# Experiment3.net
KiCad netlist of a schematic drawn in EAGLE
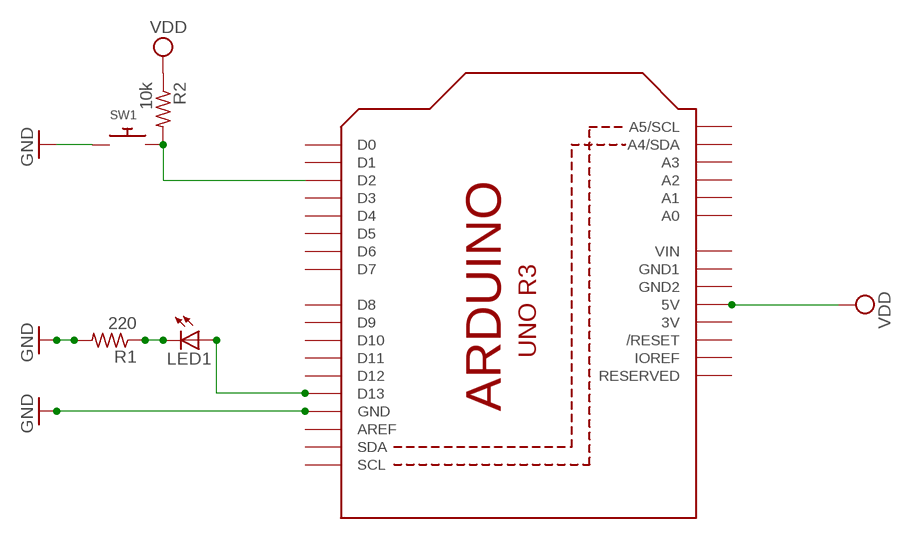
[diagram p0: schematic, sheet 1]

(export (version "E")
  (design (tool "Eeschema 10.0.6"))
  (components
    (comp (ref "LED1")
      (value "LED5MM")
      (footprint "eagle-import:LED5MM")
      (libsource (lib "eagle-import") (part "LED5MM"))
    )
    (comp (ref "R1")
      (value "220")
      (footprint "eagle-import:0204_5")
      (libsource (lib "eagle-import") (part "R-US_0204/5"))
    )
    (comp (ref "R2")
      (value "10k")
      (footprint "eagle-import:0204_5")
      (libsource (lib "eagle-import") (part "R-US_0204/5"))
    )
    (comp (ref "SW1")
      (value "SWITCH_PUSHBUTTONEVQ-PE")
      (footprint "eagle-import:TACT_PANA-EVQ")
      (libsource (lib "eagle-import") (part "SWITCH_PUSHBUTTONEVQ-PE"))
    )
    (comp (ref "U1")
      (value "ARDUINOR3-DIMENSION")
      (footprint "eagle-import:ARDUINOR3")
      (libsource (lib "eagle-import") (part "ARDUINOR3-DIMENSION"))
    )
  )
  (nets
    (net (code "1") (name "/3V") (class "Default")
      (node (ref "U1") (pin "3V") (pinfunction "3V_3V") (pintype "power_in"))
    )
    (net (code "2") (name "/GND1") (class "Default")
      (node (ref "U1") (pin "GND1") (pinfunction "GND1_GND1") (pintype "power_in"))
    )
    (net (code "3") (name "/GND2") (class "Default")
      (node (ref "U1") (pin "GND2") (pinfunction "GND2_GND2") (pintype "power_in"))
    )
    (net (code "4") (name "/VIN") (class "Default")
      (node (ref "U1") (pin "VIN") (pinfunction "VIN_VIN") (pintype "power_in"))
    )
    (net (code "5") (name "GND") (class "Default")
      (node (ref "R1") (pin "2") (pinfunction "2_2") (pintype "passive"))
      (node (ref "SW1") (pin "P$1") (pinfunction "P$1_P$1") (pintype "passive"))
      (node (ref "U1") (pin "GND") (pinfunction "GND_GND") (pintype "power_in"))
    )
    (net (code "6") (name "Net-(LED1-C)") (class "Default")
      (node (ref "LED1") (pin "K") (pinfunction "C_K") (pintype "passive"))
      (node (ref "R1") (pin "1") (pinfunction "1_1") (pintype "passive"))
    )
    (net (code "7") (name "Net-(LED1-PadA)") (class "Default")
      (node (ref "LED1") (pin "A") (pinfunction "A_A") (pintype "passive"))
      (node (ref "U1") (pin "D13") (pinfunction "D13_D13") (pintype "bidirectional"))
    )
    (net (code "8") (name "Net-(R2-Pad2)") (class "Default")
      (node (ref "R2") (pin "2") (pinfunction "2_2") (pintype "passive"))
      (node (ref "SW1") (pin "P$2") (pinfunction "P$2_P$2") (pintype "passive"))
      (node (ref "U1") (pin "D2") (pinfunction "D2_D2") (pintype "bidirectional"))
    )
    (net (code "9") (name "VDD") (class "Default")
      (node (ref "R2") (pin "1") (pinfunction "1_1") (pintype "passive"))
      (node (ref "U1") (pin "5V") (pinfunction "5V_5V") (pintype "power_in"))
    )
    (net (code "10") (name "unconnected-(U1-A4{slash}SDA-PadA4)") (class "Default")
      (node (ref "U1") (pin "A4") (pinfunction "A4/SDA_A4") (pintype "bidirectional"))
    )
    (net (code "11") (name "unconnected-(U1-A5{slash}SCL-PadA5)") (class "Default")
      (node (ref "U1") (pin "A5") (pinfunction "A5/SCL_A5") (pintype "bidirectional"))
    )
    (net (code "12") (name "unconnected-(U1-PadA0)") (class "Default")
      (node (ref "U1") (pin "A0") (pinfunction "A0_A0") (pintype "bidirectional"))
    )
    (net (code "13") (name "unconnected-(U1-PadA1)") (class "Default")
      (node (ref "U1") (pin "A1") (pinfunction "A1_A1") (pintype "bidirectional"))
    )
    (net (code "14") (name "unconnected-(U1-PadA2)") (class "Default")
      (node (ref "U1") (pin "A2") (pinfunction "A2_A2") (pintype "bidirectional"))
    )
    (net (code "15") (name "unconnected-(U1-PadA3)") (class "Default")
      (node (ref "U1") (pin "A3") (pinfunction "A3_A3") (pintype "bidirectional"))
    )
    (net (code "16") (name "unconnected-(U1-PadAREF)") (class "Default")
      (node (ref "U1") (pin "AREF") (pinfunction "AREF_AREF") (pintype "bidirectional"))
    )
    (net (code "17") (name "unconnected-(U1-PadD0)") (class "Default")
      (node (ref "U1") (pin "D0") (pinfunction "D0_D0") (pintype "bidirectional"))
    )
    (net (code "18") (name "unconnected-(U1-PadD1)") (class "Default")
      (node (ref "U1") (pin "D1") (pinfunction "D1_D1") (pintype "bidirectional"))
    )
    (net (code "19") (name "unconnected-(U1-PadD3)") (class "Default")
      (node (ref "U1") (pin "D3") (pinfunction "D3_D3") (pintype "bidirectional"))
    )
    (net (code "20") (name "unconnected-(U1-PadD4)") (class "Default")
      (node (ref "U1") (pin "D4") (pinfunction "D4_D4") (pintype "bidirectional"))
    )
    (net (code "21") (name "unconnected-(U1-PadD5)") (class "Default")
      (node (ref "U1") (pin "D5") (pinfunction "D5_D5") (pintype "bidirectional"))
    )
    (net (code "22") (name "unconnected-(U1-PadD6)") (class "Default")
      (node (ref "U1") (pin "D6") (pinfunction "D6_D6") (pintype "bidirectional"))
    )
    (net (code "23") (name "unconnected-(U1-PadD7)") (class "Default")
      (node (ref "U1") (pin "D7") (pinfunction "D7_D7") (pintype "bidirectional"))
    )
    (net (code "24") (name "unconnected-(U1-PadD8)") (class "Default")
      (node (ref "U1") (pin "D8") (pinfunction "D8_D8") (pintype "bidirectional"))
    )
    (net (code "25") (name "unconnected-(U1-PadD9)") (class "Default")
      (node (ref "U1") (pin "D9") (pinfunction "D9_D9") (pintype "bidirectional"))
    )
    (net (code "26") (name "unconnected-(U1-PadD10)") (class "Default")
      (node (ref "U1") (pin "D10") (pinfunction "D10_D10") (pintype "bidirectional"))
    )
    (net (code "27") (name "unconnected-(U1-PadD11)") (class "Default")
      (node (ref "U1") (pin "D11") (pinfunction "D11_D11") (pintype "bidirectional"))
    )
    (net (code "28") (name "unconnected-(U1-PadD12)") (class "Default")
      (node (ref "U1") (pin "D12") (pinfunction "D12_D12") (pintype "bidirectional"))
    )
    (net (code "29") (name "unconnected-(U1-PadIOREF)") (class "Default")
      (node (ref "U1") (pin "IOREF") (pinfunction "IOREF_IOREF") (pintype "output"))
    )
    (net (code "30") (name "unconnected-(U1-PadRESERVED)") (class "Default")
      (node (ref "U1") (pin "RESERVED") (pinfunction "RESERVED_RESERVED") (pintype "no_connect"))
    )
    (net (code "31") (name "unconnected-(U1-PadSCL)") (class "Default")
      (node (ref "U1") (pin "SCL") (pinfunction "SCL_SCL") (pintype "bidirectional"))
    )
    (net (code "32") (name "unconnected-(U1-PadSDA)") (class "Default")
      (node (ref "U1") (pin "SDA") (pinfunction "SDA_SDA") (pintype "bidirectional"))
    )
    (net (code "33") (name "unconnected-(U1-{slash}RESET-PadRESET)") (class "Default")
      (node (ref "U1") (pin "RESET") (pinfunction "/RESET_RESET") (pintype "bidirectional"))
    )
  )
)
